# eMMC_FLASH_INTERFACE.net
KiCad netlist of a schematic drawn in Altium Designer
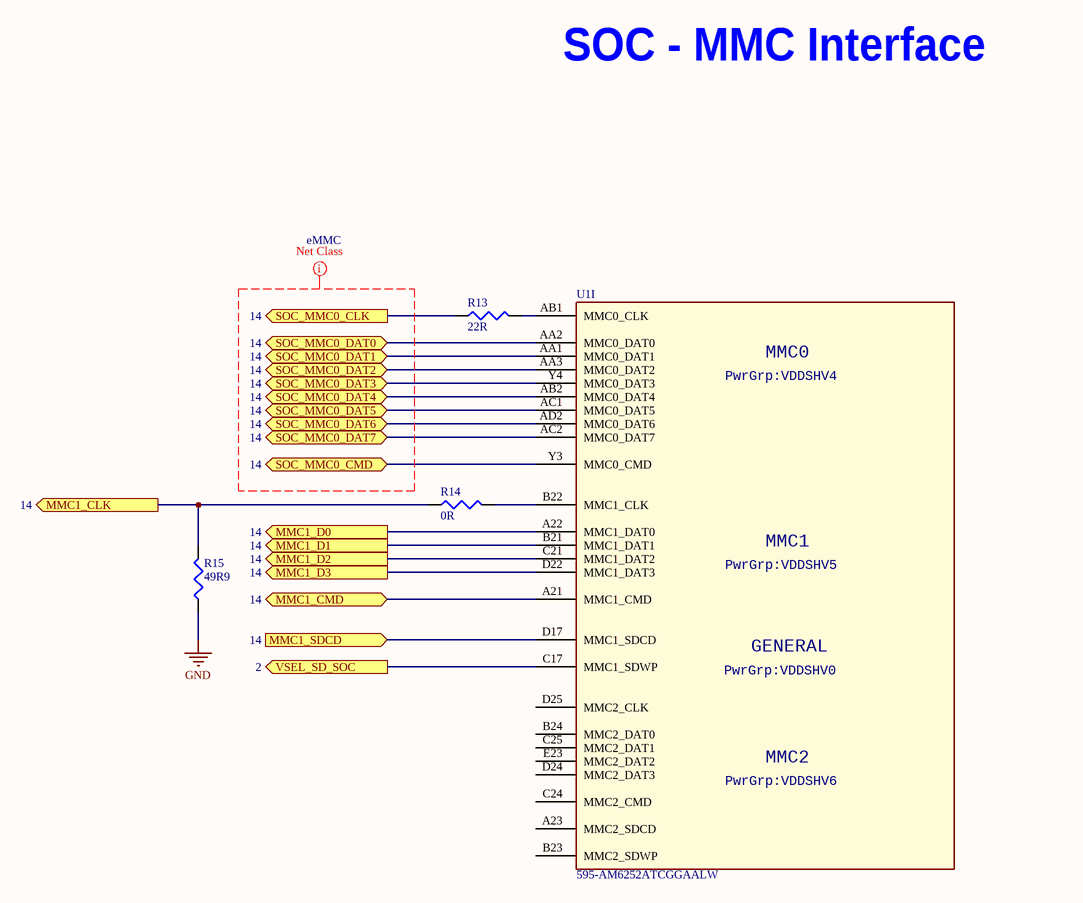
[diagram p0: eMMC FLASH INTERFACE.SchDoc]

(export (version "E")
  (design (tool "Eeschema 10.0.6"))
  (components
    (comp (ref "R13")
      (value "22R")
      (footprint "R0402")
      (description "RES 22.0 OHM 1/16W 1% 0402 SMD")
      (fields
        (field (name "MANUFACTURER") "Yageo")
        (field (name "MANUFACTURER PART NUMBER") "RC0402FR-0722RL")
      )
      (libsource (lib "Schlib AM625") (part "RC0402FR-0722RL"))
    )
    (comp (ref "R14")
      (value "0R")
      (footprint "R0402")
      (description "RES 0.0 OHM 1/16W 0402 SMD")
      (fields
        (field (name "MANUFACTURER") "Yageo")
        (field (name "MANUFACTURER PART NUMBER") "RC0402JR-070RL")
      )
      (libsource (lib "Schlib AM625") (part "RC0402JR-070RL"))
    )
    (comp (ref "R15")
      (value "49R9")
      (footprint "R0402")
      (description "RES 49.9 OHM 1/16W 1% 0402 SMD")
      (fields
        (field (name "MANUFACTURER") "Yageo")
        (field (name "MANUFACTURER PART NUMBER") "RC0402FR-0749R9L")
      )
      (libsource (lib "Schlib AM625") (part "RC0402FR-0749R9L"))
    )
    (comp (ref "U1")
      (value "AM62-EVM_BGA425")
      (footprint "BGA425C50P25X25_1300X1300X89")
      (description "ARM® Cortex®-A53 Microprocessor IC Sitara™ 2 Core, 64-Bit 1.4GHz 425-FCCSP (13x13)")
      (fields
        (field (name "MANUFACTURER") "Texas Instruments")
        (field (name "MANUFACTURER PART NUMBER") "AM6252ATCGGAALW")
        (field (name "SUPPLIER PART NUMBER 1") "595-AM6252ATCGGAALW")
      )
      (libsource (lib "Schlib AM625") (part "AM62-EVM_BGA425"))
    )
  )
  (nets
    (net (code "1") (name "/MMC1_CLK") (class "Default")
      (node (ref "R14") (pin "1") (pinfunction "1_1") (pintype "passive"))
      (node (ref "R15") (pin "2") (pinfunction "2_2") (pintype "passive"))
    )
    (net (code "2") (name "/MMC1_CMD") (class "Default")
      (node (ref "U1") (pin "A21") (pinfunction "MMC1_CMD_A21") (pintype "passive"))
    )
    (net (code "3") (name "/MMC1_D0") (class "Default")
      (node (ref "U1") (pin "A22") (pinfunction "MMC1_DAT0_A22") (pintype "passive"))
    )
    (net (code "4") (name "/MMC1_D1") (class "Default")
      (node (ref "U1") (pin "B21") (pinfunction "MMC1_DAT1_B21") (pintype "passive"))
    )
    (net (code "5") (name "/MMC1_D2") (class "Default")
      (node (ref "U1") (pin "C21") (pinfunction "MMC1_DAT2_C21") (pintype "passive"))
    )
    (net (code "6") (name "/MMC1_D3") (class "Default")
      (node (ref "U1") (pin "D22") (pinfunction "MMC1_DAT3_D22") (pintype "passive"))
    )
    (net (code "7") (name "/MMC1_SDCD") (class "Default")
      (node (ref "U1") (pin "D17") (pinfunction "MMC1_SDCD_D17") (pintype "passive"))
    )
    (net (code "8") (name "/SOC_MMC0_CLK") (class "Default")
      (node (ref "R13") (pin "1") (pinfunction "1_1") (pintype "passive"))
    )
    (net (code "9") (name "/SOC_MMC0_CMD") (class "Default")
      (node (ref "U1") (pin "Y3") (pinfunction "MMC0_CMD_Y3") (pintype "passive"))
    )
    (net (code "10") (name "/SOC_MMC0_DAT0") (class "Default")
      (node (ref "U1") (pin "AA2") (pinfunction "MMC0_DAT0_AA2") (pintype "passive"))
    )
    (net (code "11") (name "/SOC_MMC0_DAT1") (class "Default")
      (node (ref "U1") (pin "AA1") (pinfunction "MMC0_DAT1_AA1") (pintype "passive"))
    )
    (net (code "12") (name "/SOC_MMC0_DAT2") (class "Default")
      (node (ref "U1") (pin "AA3") (pinfunction "MMC0_DAT2_AA3") (pintype "passive"))
    )
    (net (code "13") (name "/SOC_MMC0_DAT3") (class "Default")
      (node (ref "U1") (pin "Y4") (pinfunction "MMC0_DAT3_Y4") (pintype "passive"))
    )
    (net (code "14") (name "/SOC_MMC0_DAT4") (class "Default")
      (node (ref "U1") (pin "AB2") (pinfunction "MMC0_DAT4_AB2") (pintype "passive"))
    )
    (net (code "15") (name "/SOC_MMC0_DAT5") (class "Default")
      (node (ref "U1") (pin "AC1") (pinfunction "MMC0_DAT5_AC1") (pintype "passive"))
    )
    (net (code "16") (name "/SOC_MMC0_DAT6") (class "Default")
      (node (ref "U1") (pin "AD2") (pinfunction "MMC0_DAT6_AD2") (pintype "passive"))
    )
    (net (code "17") (name "/SOC_MMC0_DAT7") (class "Default")
      (node (ref "U1") (pin "AC2") (pinfunction "MMC0_DAT7_AC2") (pintype "passive"))
    )
    (net (code "18") (name "/VSEL_SD_SOC") (class "Default")
      (node (ref "U1") (pin "C17") (pinfunction "MMC1_SDWP_C17") (pintype "passive"))
    )
    (net (code "19") (name "GND") (class "Default")
      (node (ref "R15") (pin "1") (pinfunction "1_1") (pintype "passive"))
    )
    (net (code "20") (name "Net-(U1I-MMC0_CLK)") (class "Default")
      (node (ref "R13") (pin "2") (pinfunction "2_2") (pintype "passive"))
      (node (ref "U1") (pin "AB1") (pinfunction "MMC0_CLK_AB1") (pintype "passive"))
    )
    (net (code "21") (name "Net-(U1I-MMC1_CLK)") (class "Default")
      (node (ref "R14") (pin "2") (pinfunction "2_2") (pintype "passive"))
      (node (ref "U1") (pin "B22") (pinfunction "MMC1_CLK_B22") (pintype "passive"))
    )
    (net (code "22") (name "unconnected-(U1I-MMC2_CLK-PadD25)") (class "Default")
      (node (ref "U1") (pin "D25") (pinfunction "MMC2_CLK_D25") (pintype "passive"))
    )
    (net (code "23") (name "unconnected-(U1I-MMC2_CMD-PadC24)") (class "Default")
      (node (ref "U1") (pin "C24") (pinfunction "MMC2_CMD_C24") (pintype "passive"))
    )
    (net (code "24") (name "unconnected-(U1I-MMC2_DAT0-PadB24)") (class "Default")
      (node (ref "U1") (pin "B24") (pinfunction "MMC2_DAT0_B24") (pintype "passive"))
    )
    (net (code "25") (name "unconnected-(U1I-MMC2_DAT1-PadC25)") (class "Default")
      (node (ref "U1") (pin "C25") (pinfunction "MMC2_DAT1_C25") (pintype "passive"))
    )
    (net (code "26") (name "unconnected-(U1I-MMC2_DAT2-PadE23)") (class "Default")
      (node (ref "U1") (pin "E23") (pinfunction "MMC2_DAT2_E23") (pintype "passive"))
    )
    (net (code "27") (name "unconnected-(U1I-MMC2_DAT3-PadD24)") (class "Default")
      (node (ref "U1") (pin "D24") (pinfunction "MMC2_DAT3_D24") (pintype "passive"))
    )
    (net (code "28") (name "unconnected-(U1I-MMC2_SDCD-PadA23)") (class "Default")
      (node (ref "U1") (pin "A23") (pinfunction "MMC2_SDCD_A23") (pintype "passive"))
    )
    (net (code "29") (name "unconnected-(U1I-MMC2_SDWP-PadB23)") (class "Default")
      (node (ref "U1") (pin "B23") (pinfunction "MMC2_SDWP_B23") (pintype "passive"))
    )
  )
)
